# snesio.net
KiCad netlist of a schematic drawn in Altium Designer
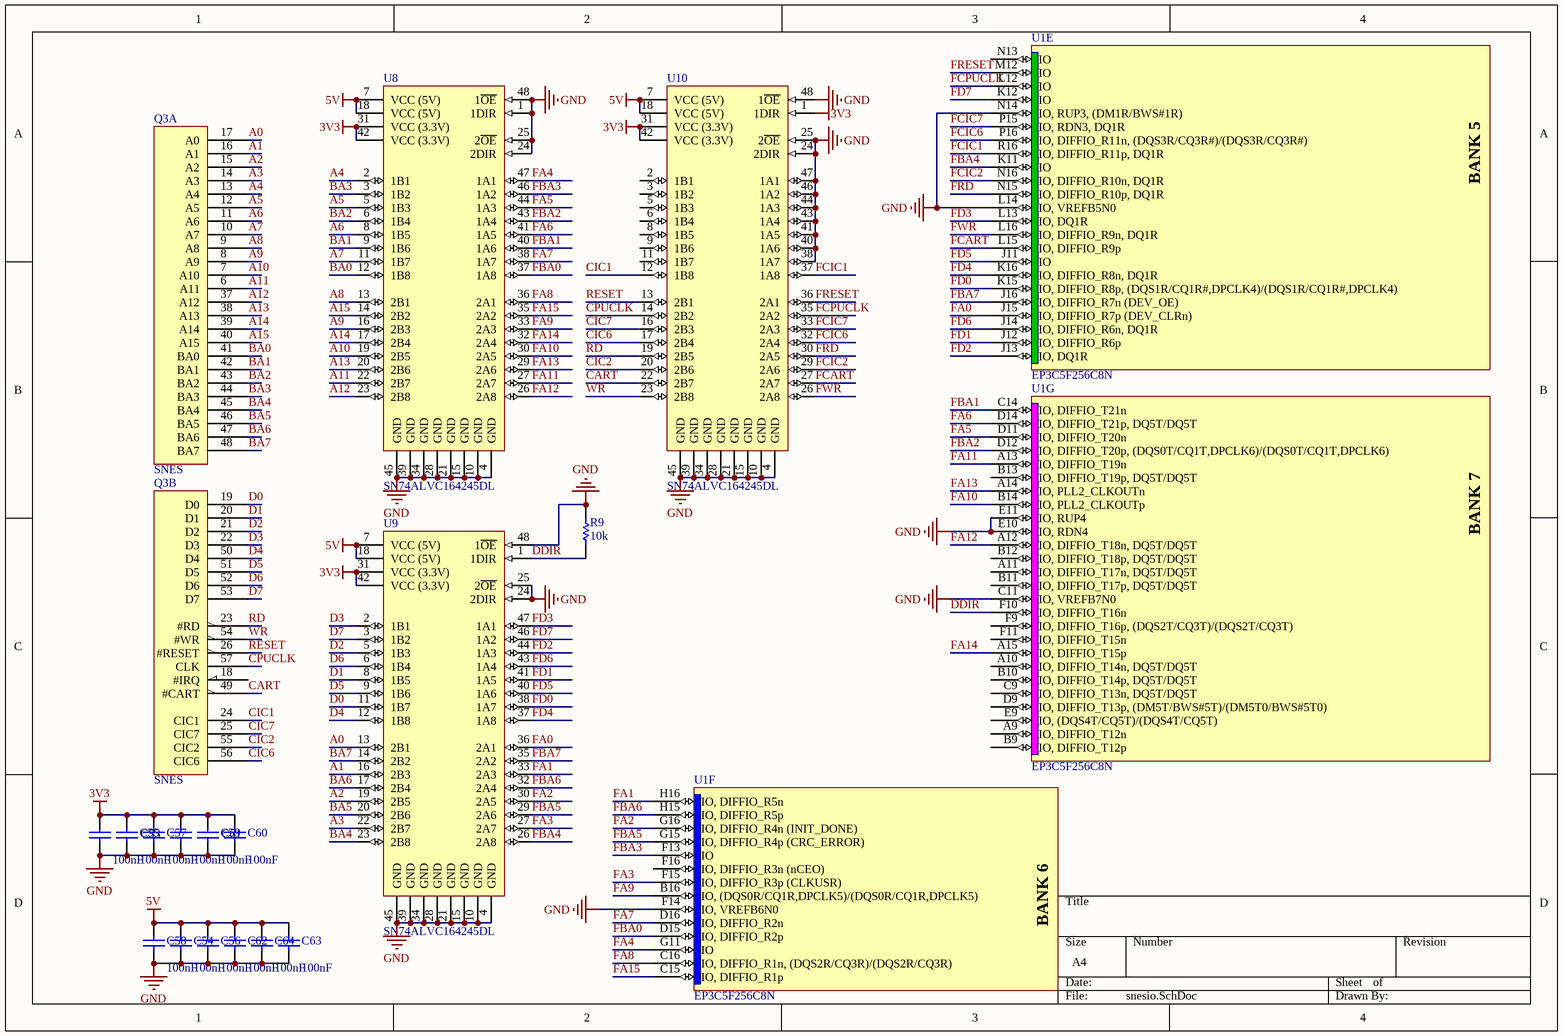
[diagram p0: snesio.SchDoc]

(export (version "E")
  (design (tool "Eeschema 10.0.6"))
  (components
    (comp (ref "C53")
      (value "100nF")
      (footprint "CAPC1005X06L")
      (description "Capacitor")
      (fields (field (name "PUBLISHER") "Altium Limited"))
      (libsource (lib "Miscellaneous Devices") (part "Cap"))
    )
    (comp (ref "C54")
      (value "100nF")
      (footprint "CAPC1005X06L")
      (description "Capacitor")
      (fields (field (name "PUBLISHER") "Altium Limited"))
      (libsource (lib "Miscellaneous Devices") (part "Cap"))
    )
    (comp (ref "C55")
      (value "100nF")
      (footprint "CAPC1005X06L")
      (description "Capacitor")
      (fields (field (name "PUBLISHER") "Altium Limited"))
      (libsource (lib "Miscellaneous Devices") (part "Cap"))
    )
    (comp (ref "C56")
      (value "100nF")
      (footprint "CAPC1005X06L")
      (description "Capacitor")
      (fields (field (name "PUBLISHER") "Altium Limited"))
      (libsource (lib "Miscellaneous Devices") (part "Cap"))
    )
    (comp (ref "C57")
      (value "100nF")
      (footprint "CAPC1005X06L")
      (description "Capacitor")
      (fields (field (name "PUBLISHER") "Altium Limited"))
      (libsource (lib "Miscellaneous Devices") (part "Cap"))
    )
    (comp (ref "C58")
      (value "100nF")
      (footprint "CAPC1005X06L")
      (description "Capacitor")
      (fields (field (name "PUBLISHER") "Altium Limited"))
      (libsource (lib "Miscellaneous Devices") (part "Cap"))
    )
    (comp (ref "C59")
      (value "100nF")
      (footprint "CAPC1005X06L")
      (description "Capacitor")
      (fields (field (name "PUBLISHER") "Altium Limited"))
      (libsource (lib "Miscellaneous Devices") (part "Cap"))
    )
    (comp (ref "C60")
      (value "100nF")
      (footprint "CAPC1005X06L")
      (description "Capacitor")
      (fields (field (name "PUBLISHER") "Altium Limited"))
      (libsource (lib "Miscellaneous Devices") (part "Cap"))
    )
    (comp (ref "C61")
      (value "100nF")
      (footprint "CAPC1005X06L")
      (description "Capacitor")
      (fields (field (name "PUBLISHER") "Altium Limited"))
      (libsource (lib "Miscellaneous Devices") (part "Cap"))
    )
    (comp (ref "C62")
      (value "100nF")
      (footprint "CAPC1005X06L")
      (description "Capacitor")
      (fields (field (name "PUBLISHER") "Altium Limited"))
      (libsource (lib "Miscellaneous Devices") (part "Cap"))
    )
    (comp (ref "C63")
      (value "100nF")
      (footprint "CAPC1005X06L")
      (description "Capacitor")
      (fields (field (name "PUBLISHER") "Altium Limited"))
      (libsource (lib "Miscellaneous Devices") (part "Cap"))
    )
    (comp (ref "C64")
      (value "100nF")
      (footprint "CAPC1005X06L")
      (description "Capacitor")
      (fields (field (name "PUBLISHER") "Altium Limited"))
      (libsource (lib "Miscellaneous Devices") (part "Cap"))
    )
    (comp (ref "Q3") (value "SNES") (footprint "SNES") (libsource (lib "parts") (part "SNES")))
    (comp (ref "R9")
      (value "10k")
      (footprint "RESC2012X70N")
      (description "Resistor")
      (fields (field (name "Comment") "Res1") (field (name "PUBLISHER") "Altium Limited"))
      (libsource (lib "Miscellaneous Devices") (part "Res1"))
    )
    (comp (ref "U1")
      (value "EP3C5F256C8N")
      (footprint "FBGA256-2")
      (fields (field (name "PUBLISHER") "Altium Limited"))
      (libsource (lib "Altera Cyclone III") (part "EP3C5F256C8N"))
    )
    (comp (ref "U8")
      (value "SN74ALVC164245DL")
      (footprint "DL048")
      (description "16-Bit 3.3-V to 5-V Level Shifting Transceiver with 3-State Outputs")
      (fields (field (name "PUBLISHER") "Altium Limited"))
      (libsource (lib "TI Interface Line Transceiver") (part "SN74ALVC164245DL"))
    )
    (comp (ref "U9")
      (value "SN74ALVC164245DL")
      (footprint "DL048")
      (description "16-Bit 3.3-V to 5-V Level Shifting Transceiver with 3-State Outputs")
      (fields (field (name "PUBLISHER") "Altium Limited"))
      (libsource (lib "TI Interface Line Transceiver") (part "SN74ALVC164245DL"))
    )
    (comp (ref "U10")
      (value "SN74ALVC164245DL")
      (footprint "DL048")
      (description "16-Bit 3.3-V to 5-V Level Shifting Transceiver with 3-State Outputs")
      (fields (field (name "PUBLISHER") "Altium Limited"))
      (libsource (lib "TI Interface Line Transceiver") (part "SN74ALVC164245DL"))
    )
  )
  (nets
    (net (code "1") (name "/A0") (class "Default")
      (node (ref "Q3") (pin "17") (pinfunction "A0_17") (pintype "passive"))
      (node (ref "U9") (pin "13") (pinfunction "2B1_13") (pintype "bidirectional"))
    )
    (net (code "2") (name "/A1") (class "Default")
      (node (ref "Q3") (pin "16") (pinfunction "A1_16") (pintype "passive"))
      (node (ref "U9") (pin "16") (pinfunction "2B3_16") (pintype "bidirectional"))
    )
    (net (code "3") (name "/A2") (class "Default")
      (node (ref "Q3") (pin "15") (pinfunction "A2_15") (pintype "passive"))
      (node (ref "U9") (pin "19") (pinfunction "2B5_19") (pintype "bidirectional"))
    )
    (net (code "4") (name "/A3") (class "Default")
      (node (ref "Q3") (pin "14") (pinfunction "A3_14") (pintype "passive"))
      (node (ref "U9") (pin "22") (pinfunction "2B7_22") (pintype "bidirectional"))
    )
    (net (code "5") (name "/A4") (class "Default")
      (node (ref "Q3") (pin "13") (pinfunction "A4_13") (pintype "passive"))
      (node (ref "U8") (pin "2") (pinfunction "1B1_2") (pintype "bidirectional"))
    )
    (net (code "6") (name "/A5") (class "Default")
      (node (ref "Q3") (pin "12") (pinfunction "A5_12") (pintype "passive"))
      (node (ref "U8") (pin "5") (pinfunction "1B3_5") (pintype "bidirectional"))
    )
    (net (code "7") (name "/A6") (class "Default")
      (node (ref "Q3") (pin "11") (pinfunction "A6_11") (pintype "passive"))
      (node (ref "U8") (pin "8") (pinfunction "1B5_8") (pintype "bidirectional"))
    )
    (net (code "8") (name "/A7") (class "Default")
      (node (ref "Q3") (pin "10") (pinfunction "A7_10") (pintype "passive"))
      (node (ref "U8") (pin "11") (pinfunction "1B7_11") (pintype "bidirectional"))
    )
    (net (code "9") (name "/A8") (class "Default")
      (node (ref "Q3") (pin "9") (pinfunction "A8_9") (pintype "passive"))
      (node (ref "U8") (pin "13") (pinfunction "2B1_13") (pintype "bidirectional"))
    )
    (net (code "10") (name "/A9") (class "Default")
      (node (ref "Q3") (pin "8") (pinfunction "A9_8") (pintype "passive"))
      (node (ref "U8") (pin "16") (pinfunction "2B3_16") (pintype "bidirectional"))
    )
    (net (code "11") (name "/A10") (class "Default")
      (node (ref "Q3") (pin "7") (pinfunction "A10_7") (pintype "passive"))
      (node (ref "U8") (pin "19") (pinfunction "2B5_19") (pintype "bidirectional"))
    )
    (net (code "12") (name "/A11") (class "Default")
      (node (ref "Q3") (pin "6") (pinfunction "A11_6") (pintype "passive"))
      (node (ref "U8") (pin "22") (pinfunction "2B7_22") (pintype "bidirectional"))
    )
    (net (code "13") (name "/A12") (class "Default")
      (node (ref "Q3") (pin "37") (pinfunction "A12_37") (pintype "passive"))
      (node (ref "U8") (pin "23") (pinfunction "2B8_23") (pintype "bidirectional"))
    )
    (net (code "14") (name "/A13") (class "Default")
      (node (ref "Q3") (pin "38") (pinfunction "A13_38") (pintype "passive"))
      (node (ref "U8") (pin "20") (pinfunction "2B6_20") (pintype "bidirectional"))
    )
    (net (code "15") (name "/A14") (class "Default")
      (node (ref "Q3") (pin "39") (pinfunction "A14_39") (pintype "passive"))
      (node (ref "U8") (pin "17") (pinfunction "2B4_17") (pintype "bidirectional"))
    )
    (net (code "16") (name "/A15") (class "Default")
      (node (ref "Q3") (pin "40") (pinfunction "A15_40") (pintype "passive"))
      (node (ref "U8") (pin "14") (pinfunction "2B2_14") (pintype "bidirectional"))
    )
    (net (code "17") (name "/BA0") (class "Default")
      (node (ref "Q3") (pin "41") (pinfunction "BA0_41") (pintype "passive"))
      (node (ref "U8") (pin "12") (pinfunction "1B8_12") (pintype "bidirectional"))
    )
    (net (code "18") (name "/BA1") (class "Default")
      (node (ref "Q3") (pin "42") (pinfunction "BA1_42") (pintype "passive"))
      (node (ref "U8") (pin "9") (pinfunction "1B6_9") (pintype "bidirectional"))
    )
    (net (code "19") (name "/BA2") (class "Default")
      (node (ref "Q3") (pin "43") (pinfunction "BA2_43") (pintype "passive"))
      (node (ref "U8") (pin "6") (pinfunction "1B4_6") (pintype "bidirectional"))
    )
    (net (code "20") (name "/BA3") (class "Default")
      (node (ref "Q3") (pin "44") (pinfunction "BA3_44") (pintype "passive"))
      (node (ref "U8") (pin "3") (pinfunction "1B2_3") (pintype "bidirectional"))
    )
    (net (code "21") (name "/BA4") (class "Default")
      (node (ref "Q3") (pin "45") (pinfunction "BA4_45") (pintype "passive"))
      (node (ref "U9") (pin "23") (pinfunction "2B8_23") (pintype "bidirectional"))
    )
    (net (code "22") (name "/BA5") (class "Default")
      (node (ref "Q3") (pin "46") (pinfunction "BA5_46") (pintype "passive"))
      (node (ref "U9") (pin "20") (pinfunction "2B6_20") (pintype "bidirectional"))
    )
    (net (code "23") (name "/BA6") (class "Default")
      (node (ref "Q3") (pin "47") (pinfunction "BA6_47") (pintype "passive"))
      (node (ref "U9") (pin "17") (pinfunction "2B4_17") (pintype "bidirectional"))
    )
    (net (code "24") (name "/BA7") (class "Default")
      (node (ref "Q3") (pin "48") (pinfunction "BA7_48") (pintype "passive"))
      (node (ref "U9") (pin "14") (pinfunction "2B2_14") (pintype "bidirectional"))
    )
    (net (code "25") (name "/CART") (class "Default")
      (node (ref "Q3") (pin "49") (pinfunction "#CART_49") (pintype "passive"))
      (node (ref "U10") (pin "22") (pinfunction "2B7_22") (pintype "bidirectional"))
    )
    (net (code "26") (name "/CIC1") (class "Default")
      (node (ref "Q3") (pin "24") (pinfunction "CIC1_24") (pintype "passive"))
      (node (ref "U10") (pin "12") (pinfunction "1B8_12") (pintype "bidirectional"))
    )
    (net (code "27") (name "/CIC2") (class "Default")
      (node (ref "Q3") (pin "55") (pinfunction "CIC2_55") (pintype "passive"))
      (node (ref "U10") (pin "20") (pinfunction "2B6_20") (pintype "bidirectional"))
    )
    (net (code "28") (name "/CIC6") (class "Default")
      (node (ref "Q3") (pin "56") (pinfunction "CIC6_56") (pintype "passive"))
      (node (ref "U10") (pin "17") (pinfunction "2B4_17") (pintype "bidirectional"))
    )
    (net (code "29") (name "/CIC7") (class "Default")
      (node (ref "Q3") (pin "25") (pinfunction "CIC7_25") (pintype "passive"))
      (node (ref "U10") (pin "16") (pinfunction "2B3_16") (pintype "bidirectional"))
    )
    (net (code "30") (name "/CPUCLK") (class "Default")
      (node (ref "Q3") (pin "57") (pinfunction "CLK_57") (pintype "passive"))
      (node (ref "U10") (pin "14") (pinfunction "2B2_14") (pintype "bidirectional"))
    )
    (net (code "31") (name "/D0") (class "Default")
      (node (ref "Q3") (pin "19") (pinfunction "D0_19") (pintype "passive"))
      (node (ref "U9") (pin "11") (pinfunction "1B7_11") (pintype "bidirectional"))
    )
    (net (code "32") (name "/D1") (class "Default")
      (node (ref "Q3") (pin "20") (pinfunction "D1_20") (pintype "passive"))
      (node (ref "U9") (pin "8") (pinfunction "1B5_8") (pintype "bidirectional"))
    )
    (net (code "33") (name "/D2") (class "Default")
      (node (ref "Q3") (pin "21") (pinfunction "D2_21") (pintype "passive"))
      (node (ref "U9") (pin "5") (pinfunction "1B3_5") (pintype "bidirectional"))
    )
    (net (code "34") (name "/D3") (class "Default")
      (node (ref "Q3") (pin "22") (pinfunction "D3_22") (pintype "passive"))
      (node (ref "U9") (pin "2") (pinfunction "1B1_2") (pintype "bidirectional"))
    )
    (net (code "35") (name "/D4") (class "Default")
      (node (ref "Q3") (pin "50") (pinfunction "D4_50") (pintype "passive"))
      (node (ref "U9") (pin "12") (pinfunction "1B8_12") (pintype "bidirectional"))
    )
    (net (code "36") (name "/D5") (class "Default")
      (node (ref "Q3") (pin "51") (pinfunction "D5_51") (pintype "passive"))
      (node (ref "U9") (pin "9") (pinfunction "1B6_9") (pintype "bidirectional"))
    )
    (net (code "37") (name "/D6") (class "Default")
      (node (ref "Q3") (pin "52") (pinfunction "D6_52") (pintype "passive"))
      (node (ref "U9") (pin "6") (pinfunction "1B4_6") (pintype "bidirectional"))
    )
    (net (code "38") (name "/D7") (class "Default")
      (node (ref "Q3") (pin "53") (pinfunction "D7_53") (pintype "passive"))
      (node (ref "U9") (pin "3") (pinfunction "1B2_3") (pintype "bidirectional"))
    )
    (net (code "39") (name "/DDIR") (class "Default")
      (node (ref "R9") (pin "2") (pinfunction "2_2") (pintype "passive"))
      (node (ref "U1") (pin "F10") (pinfunction "IO,_DIFFIO_T16n_F10") (pintype "bidirectional"))
      (node (ref "U9") (pin "1") (pinfunction "1DIR_1") (pintype "input"))
    )
    (net (code "40") (name "/FA0") (class "Default")
      (node (ref "U1") (pin "J15") (pinfunction "IO,_DIFFIO_R7p_(DEV_CLRn)_J15") (pintype "bidirectional"))
      (node (ref "U9") (pin "36") (pinfunction "2A1_36") (pintype "bidirectional"))
    )
    (net (code "41") (name "/FA1") (class "Default")
      (node (ref "U1") (pin "H16") (pinfunction "IO,_DIFFIO_R5n_H16") (pintype "bidirectional"))
      (node (ref "U9") (pin "33") (pinfunction "2A3_33") (pintype "bidirectional"))
    )
    (net (code "42") (name "/FA2") (class "Default")
      (node (ref "U1") (pin "G16") (pinfunction "IO,_DIFFIO_R4n_(INIT_DONE)_G16") (pintype "bidirectional"))
      (node (ref "U9") (pin "30") (pinfunction "2A5_30") (pintype "bidirectional"))
    )
    (net (code "43") (name "/FA3") (class "Default")
      (node (ref "U1") (pin "F15") (pinfunction "IO,_DIFFIO_R3p_(CLKUSR)_F15") (pintype "bidirectional"))
      (node (ref "U9") (pin "27") (pinfunction "2A7_27") (pintype "bidirectional"))
    )
    (net (code "44") (name "/FA4") (class "Default")
      (node (ref "U1") (pin "G11") (pinfunction "IO_G11") (pintype "bidirectional"))
      (node (ref "U8") (pin "47") (pinfunction "1A1_47") (pintype "bidirectional"))
    )
    (net (code "45") (name "/FA5") (class "Default")
      (node (ref "U1") (pin "D11") (pinfunction "IO,_DIFFIO_T20n_D11") (pintype "bidirectional"))
      (node (ref "U8") (pin "44") (pinfunction "1A3_44") (pintype "bidirectional"))
    )
    (net (code "46") (name "/FA6") (class "Default")
      (node (ref "U1") (pin "D14") (pinfunction "IO,_DIFFIO_T21p,_DQ5T/DQ5T_D14") (pintype "bidirectional"))
      (node (ref "U8") (pin "41") (pinfunction "1A5_41") (pintype "bidirectional"))
    )
    (net (code "47") (name "/FA7") (class "Default")
      (node (ref "U1") (pin "D16") (pinfunction "IO,_DIFFIO_R2n_D16") (pintype "bidirectional"))
      (node (ref "U8") (pin "38") (pinfunction "1A7_38") (pintype "bidirectional"))
    )
    (net (code "48") (name "/FA8") (class "Default")
      (node (ref "U1") (pin "C16") (pinfunction "IO,_DIFFIO_R1n,_(DQS2R/CQ3R)/(DQS2R/CQ3R)_C16") (pintype "bidirectional"))
      (node (ref "U8") (pin "36") (pinfunction "2A1_36") (pintype "bidirectional"))
    )
    (net (code "49") (name "/FA9") (class "Default")
      (node (ref "U1") (pin "B16") (pinfunction "IO,_(DQS0R/CQ1R,DPCLK5)/(DQS0R/CQ1R,DPCLK5)_B16") (pintype "bidirectional"))
      (node (ref "U8") (pin "33") (pinfunction "2A3_33") (pintype "bidirectional"))
    )
    (net (code "50") (name "/FA10") (class "Default")
      (node (ref "U1") (pin "B14") (pinfunction "IO,_PLL2_CLKOUTp_B14") (pintype "bidirectional"))
      (node (ref "U8") (pin "30") (pinfunction "2A5_30") (pintype "bidirectional"))
    )
    (net (code "51") (name "/FA11") (class "Default")
      (node (ref "U1") (pin "A13") (pinfunction "IO,_DIFFIO_T19n_A13") (pintype "bidirectional"))
      (node (ref "U8") (pin "27") (pinfunction "2A7_27") (pintype "bidirectional"))
    )
    (net (code "52") (name "/FA12") (class "Default")
      (node (ref "U1") (pin "A12") (pinfunction "IO,_DIFFIO_T18n,_DQ5T/DQ5T_A12") (pintype "bidirectional"))
      (node (ref "U8") (pin "26") (pinfunction "2A8_26") (pintype "bidirectional"))
    )
    (net (code "53") (name "/FA13") (class "Default")
      (node (ref "U1") (pin "A14") (pinfunction "IO,_PLL2_CLKOUTn_A14") (pintype "bidirectional"))
      (node (ref "U8") (pin "29") (pinfunction "2A6_29") (pintype "bidirectional"))
    )
    (net (code "54") (name "/FA14") (class "Default")
      (node (ref "U1") (pin "A15") (pinfunction "IO,_DIFFIO_T15p_A15") (pintype "bidirectional"))
      (node (ref "U8") (pin "32") (pinfunction "2A4_32") (pintype "bidirectional"))
    )
    (net (code "55") (name "/FA15") (class "Default")
      (node (ref "U1") (pin "C15") (pinfunction "IO,_DIFFIO_R1p_C15") (pintype "bidirectional"))
      (node (ref "U8") (pin "35") (pinfunction "2A2_35") (pintype "bidirectional"))
    )
    (net (code "56") (name "/FBA0") (class "Default")
      (node (ref "U1") (pin "D15") (pinfunction "IO,_DIFFIO_R2p_D15") (pintype "bidirectional"))
      (node (ref "U8") (pin "37") (pinfunction "1A8_37") (pintype "bidirectional"))
    )
    (net (code "57") (name "/FBA1") (class "Default")
      (node (ref "U1") (pin "C14") (pinfunction "IO,_DIFFIO_T21n_C14") (pintype "bidirectional"))
      (node (ref "U8") (pin "40") (pinfunction "1A6_40") (pintype "bidirectional"))
    )
    (net (code "58") (name "/FBA2") (class "Default")
      (node (ref "U1") (pin "D12") (pinfunction "IO,_DIFFIO_T20p,_(DQS0T/CQ1T,DPCLK6)/(DQS0T/CQ1T,DPCLK6)_D12") (pintype "bidirectional"))
      (node (ref "U8") (pin "43") (pinfunction "1A4_43") (pintype "bidirectional"))
    )
    (net (code "59") (name "/FBA3") (class "Default")
      (node (ref "U1") (pin "F13") (pinfunction "IO_F13") (pintype "bidirectional"))
      (node (ref "U8") (pin "46") (pinfunction "1A2_46") (pintype "bidirectional"))
    )
    (net (code "60") (name "/FBA4") (class "Default")
      (node (ref "U1") (pin "K11") (pinfunction "IO_K11") (pintype "bidirectional"))
      (node (ref "U9") (pin "26") (pinfunction "2A8_26") (pintype "bidirectional"))
    )
    (net (code "61") (name "/FBA5") (class "Default")
      (node (ref "U1") (pin "G15") (pinfunction "IO,_DIFFIO_R4p_(CRC_ERROR)_G15") (pintype "bidirectional"))
      (node (ref "U9") (pin "29") (pinfunction "2A6_29") (pintype "bidirectional"))
    )
    (net (code "62") (name "/FBA6") (class "Default")
      (node (ref "U1") (pin "H15") (pinfunction "IO,_DIFFIO_R5p_H15") (pintype "bidirectional"))
      (node (ref "U9") (pin "32") (pinfunction "2A4_32") (pintype "bidirectional"))
    )
    (net (code "63") (name "/FBA7") (class "Default")
      (node (ref "U1") (pin "J16") (pinfunction "IO,_DIFFIO_R7n_(DEV_OE)_J16") (pintype "bidirectional"))
      (node (ref "U9") (pin "35") (pinfunction "2A2_35") (pintype "bidirectional"))
    )
    (net (code "64") (name "/FCART") (class "Default")
      (node (ref "U1") (pin "L15") (pinfunction "IO,_DIFFIO_R9p_L15") (pintype "bidirectional"))
      (node (ref "U10") (pin "27") (pinfunction "2A7_27") (pintype "bidirectional"))
    )
    (net (code "65") (name "/FCIC1") (class "Default")
      (node (ref "U1") (pin "R16") (pinfunction "IO,_DIFFIO_R11p,_DQ1R_R16") (pintype "bidirectional"))
      (node (ref "U10") (pin "37") (pinfunction "1A8_37") (pintype "bidirectional"))
    )
    (net (code "66") (name "/FCIC2") (class "Default")
      (node (ref "U1") (pin "N16") (pinfunction "IO,_DIFFIO_R10n,_DQ1R_N16") (pintype "bidirectional"))
      (node (ref "U10") (pin "29") (pinfunction "2A6_29") (pintype "bidirectional"))
    )
    (net (code "67") (name "/FCIC6") (class "Default")
      (node (ref "U1") (pin "P16") (pinfunction "IO,_DIFFIO_R11n,_(DQS3R/CQ3R#)/(DQS3R/CQ3R#)_P16") (pintype "bidirectional"))
      (node (ref "U10") (pin "32") (pinfunction "2A4_32") (pintype "bidirectional"))
    )
    (net (code "68") (name "/FCIC7") (class "Default")
      (node (ref "U1") (pin "P15") (pinfunction "IO,_RDN3,_DQ1R_P15") (pintype "bidirectional"))
      (node (ref "U10") (pin "33") (pinfunction "2A3_33") (pintype "bidirectional"))
    )
    (net (code "69") (name "/FCPUCLK") (class "Default")
      (node (ref "U1") (pin "L12") (pinfunction "IO_L12") (pintype "bidirectional"))
      (node (ref "U10") (pin "35") (pinfunction "2A2_35") (pintype "bidirectional"))
    )
    (net (code "70") (name "/FD0") (class "Default")
      (node (ref "U1") (pin "K15") (pinfunction "IO,_DIFFIO_R8p,_(DQS1R/CQ1R#,DPCLK4)/(DQS1R/CQ1R#,DPCLK4)_K15") (pintype "bidirectional"))
      (node (ref "U9") (pin "38") (pinfunction "1A7_38") (pintype "bidirectional"))
    )
    (net (code "71") (name "/FD1") (class "Default")
      (node (ref "U1") (pin "J12") (pinfunction "IO,_DIFFIO_R6p_J12") (pintype "bidirectional"))
      (node (ref "U9") (pin "41") (pinfunction "1A5_41") (pintype "bidirectional"))
    )
    (net (code "72") (name "/FD2") (class "Default")
      (node (ref "U1") (pin "J13") (pinfunction "IO,_DQ1R_J13") (pintype "bidirectional"))
      (node (ref "U9") (pin "44") (pinfunction "1A3_44") (pintype "bidirectional"))
    )
    (net (code "73") (name "/FD3") (class "Default")
      (node (ref "U1") (pin "L13") (pinfunction "IO,_DQ1R_L13") (pintype "bidirectional"))
      (node (ref "U9") (pin "47") (pinfunction "1A1_47") (pintype "bidirectional"))
    )
    (net (code "74") (name "/FD4") (class "Default")
      (node (ref "U1") (pin "K16") (pinfunction "IO,_DIFFIO_R8n,_DQ1R_K16") (pintype "bidirectional"))
      (node (ref "U9") (pin "37") (pinfunction "1A8_37") (pintype "bidirectional"))
    )
    (net (code "75") (name "/FD5") (class "Default")
      (node (ref "U1") (pin "J11") (pinfunction "IO_J11") (pintype "bidirectional"))
      (node (ref "U9") (pin "40") (pinfunction "1A6_40") (pintype "bidirectional"))
    )
    (net (code "76") (name "/FD6") (class "Default")
      (node (ref "U1") (pin "J14") (pinfunction "IO,_DIFFIO_R6n,_DQ1R_J14") (pintype "bidirectional"))
      (node (ref "U9") (pin "43") (pinfunction "1A4_43") (pintype "bidirectional"))
    )
    (net (code "77") (name "/FD7") (class "Default")
      (node (ref "U1") (pin "K12") (pinfunction "IO_K12") (pintype "bidirectional"))
      (node (ref "U9") (pin "46") (pinfunction "1A2_46") (pintype "bidirectional"))
    )
    (net (code "78") (name "/FRD") (class "Default")
      (node (ref "U1") (pin "N15") (pinfunction "IO,_DIFFIO_R10p,_DQ1R_N15") (pintype "bidirectional"))
      (node (ref "U10") (pin "30") (pinfunction "2A5_30") (pintype "bidirectional"))
    )
    (net (code "79") (name "/FRESET") (class "Default")
      (node (ref "U1") (pin "M12") (pinfunction "IO_M12") (pintype "bidirectional"))
      (node (ref "U10") (pin "36") (pinfunction "2A1_36") (pintype "bidirectional"))
    )
    (net (code "80") (name "/FWR") (class "Default")
      (node (ref "U1") (pin "L16") (pinfunction "IO,_DIFFIO_R9n,_DQ1R_L16") (pintype "bidirectional"))
      (node (ref "U10") (pin "26") (pinfunction "2A8_26") (pintype "bidirectional"))
    )
    (net (code "81") (name "/RD") (class "Default")
      (node (ref "Q3") (pin "23") (pinfunction "#RD_23") (pintype "passive"))
      (node (ref "U10") (pin "19") (pinfunction "2B5_19") (pintype "bidirectional"))
    )
    (net (code "82") (name "/RESET") (class "Default")
      (node (ref "Q3") (pin "26") (pinfunction "#RESET_26") (pintype "passive"))
      (node (ref "U10") (pin "13") (pinfunction "2B1_13") (pintype "bidirectional"))
    )
    (net (code "83") (name "/WR") (class "Default")
      (node (ref "Q3") (pin "54") (pinfunction "#WR_54") (pintype "passive"))
      (node (ref "U10") (pin "23") (pinfunction "2B8_23") (pintype "bidirectional"))
    )
    (net (code "84") (name "3V3") (class "Default")
      (node (ref "C53") (pin "2") (pinfunction "2_2") (pintype "passive"))
      (node (ref "C55") (pin "2") (pinfunction "2_2") (pintype "passive"))
      (node (ref "C57") (pin "2") (pinfunction "2_2") (pintype "passive"))
      (node (ref "C59") (pin "2") (pinfunction "2_2") (pintype "passive"))
      (node (ref "C60") (pin "2") (pinfunction "2_2") (pintype "passive"))
      (node (ref "C61") (pin "2") (pinfunction "2_2") (pintype "passive"))
      (node (ref "U10") (pin "1") (pinfunction "1DIR_1") (pintype "input"))
      (node (ref "U10") (pin "31") (pinfunction "VCC_(3.3V)_31") (pintype "power_in"))
      (node (ref "U10") (pin "42") (pinfunction "VCC_(3.3V)_42") (pintype "power_in"))
      (node (ref "U8") (pin "31") (pinfunction "VCC_(3.3V)_31") (pintype "power_in"))
      (node (ref "U8") (pin "42") (pinfunction "VCC_(3.3V)_42") (pintype "power_in"))
      (node (ref "U9") (pin "31") (pinfunction "VCC_(3.3V)_31") (pintype "power_in"))
      (node (ref "U9") (pin "42") (pinfunction "VCC_(3.3V)_42") (pintype "power_in"))
    )
    (net (code "85") (name "5V") (class "Default")
      (node (ref "C54") (pin "2") (pinfunction "2_2") (pintype "passive"))
      (node (ref "C56") (pin "2") (pinfunction "2_2") (pintype "passive"))
      (node (ref "C58") (pin "2") (pinfunction "2_2") (pintype "passive"))
      (node (ref "C62") (pin "2") (pinfunction "2_2") (pintype "passive"))
      (node (ref "C63") (pin "2") (pinfunction "2_2") (pintype "passive"))
      (node (ref "C64") (pin "2") (pinfunction "2_2") (pintype "passive"))
      (node (ref "U10") (pin "18") (pinfunction "VCC_(5V)_18") (pintype "power_in"))
      (node (ref "U10") (pin "7") (pinfunction "VCC_(5V)_7") (pintype "power_in"))
      (node (ref "U8") (pin "18") (pinfunction "VCC_(5V)_18") (pintype "power_in"))
      (node (ref "U8") (pin "7") (pinfunction "VCC_(5V)_7") (pintype "power_in"))
      (node (ref "U9") (pin "18") (pinfunction "VCC_(5V)_18") (pintype "power_in"))
      (node (ref "U9") (pin "7") (pinfunction "VCC_(5V)_7") (pintype "power_in"))
    )
    (net (code "86") (name "GND") (class "Default")
      (node (ref "C53") (pin "1") (pinfunction "1_1") (pintype "passive"))
      (node (ref "C54") (pin "1") (pinfunction "1_1") (pintype "passive"))
      (node (ref "C55") (pin "1") (pinfunction "1_1") (pintype "passive"))
      (node (ref "C56") (pin "1") (pinfunction "1_1") (pintype "passive"))
      (node (ref "C57") (pin "1") (pinfunction "1_1") (pintype "passive"))
      (node (ref "C58") (pin "1") (pinfunction "1_1") (pintype "passive"))
      (node (ref "C59") (pin "1") (pinfunction "1_1") (pintype "passive"))
      (node (ref "C60") (pin "1") (pinfunction "1_1") (pintype "passive"))
      (node (ref "C61") (pin "1") (pinfunction "1_1") (pintype "passive"))
      (node (ref "C62") (pin "1") (pinfunction "1_1") (pintype "passive"))
      (node (ref "C63") (pin "1") (pinfunction "1_1") (pintype "passive"))
      (node (ref "C64") (pin "1") (pinfunction "1_1") (pintype "passive"))
      (node (ref "R9") (pin "1") (pinfunction "1_1") (pintype "passive"))
      (node (ref "U1") (pin "C11") (pinfunction "IO,_VREFB7N0_C11") (pintype "bidirectional"))
      (node (ref "U1") (pin "E10") (pinfunction "IO,_RDN4_E10") (pintype "bidirectional"))
      (node (ref "U1") (pin "E11") (pinfunction "IO,_RUP4_E11") (pintype "bidirectional"))
      (node (ref "U1") (pin "F14") (pinfunction "IO,_VREFB6N0_F14") (pintype "bidirectional"))
      (node (ref "U1") (pin "L14") (pinfunction "IO,_VREFB5N0_L14") (pintype "bidirectional"))
      (node (ref "U1") (pin "N14") (pinfunction "IO,_RUP3,_(DM1R/BWS#1R)_N14") (pintype "bidirectional"))
      (node (ref "U10") (pin "10") (pinfunction "GND_10") (pintype "power_in"))
      (node (ref "U10") (pin "15") (pinfunction "GND_15") (pintype "power_in"))
      (node (ref "U10") (pin "21") (pinfunction "GND_21") (pintype "power_in"))
      (node (ref "U10") (pin "24") (pinfunction "2DIR_24") (pintype "input"))
      (node (ref "U10") (pin "25") (pinfunction "2~{OE}_25") (pintype "input"))
      (node (ref "U10") (pin "28") (pinfunction "GND_28") (pintype "power_in"))
      (node (ref "U10") (pin "34") (pinfunction "GND_34") (pintype "power_in"))
      (node (ref "U10") (pin "38") (pinfunction "1A7_38") (pintype "bidirectional"))
      (node (ref "U10") (pin "39") (pinfunction "GND_39") (pintype "power_in"))
      (node (ref "U10") (pin "4") (pinfunction "GND_4") (pintype "power_in"))
      (node (ref "U10") (pin "40") (pinfunction "1A6_40") (pintype "bidirectional"))
      (node (ref "U10") (pin "41") (pinfunction "1A5_41") (pintype "bidirectional"))
      (node (ref "U10") (pin "43") (pinfunction "1A4_43") (pintype "bidirectional"))
      (node (ref "U10") (pin "44") (pinfunction "1A3_44") (pintype "bidirectional"))
      (node (ref "U10") (pin "45") (pinfunction "GND_45") (pintype "power_in"))
      (node (ref "U10") (pin "46") (pinfunction "1A2_46") (pintype "bidirectional"))
      (node (ref "U10") (pin "47") (pinfunction "1A1_47") (pintype "bidirectional"))
      (node (ref "U10") (pin "48") (pinfunction "1~{OE}_48") (pintype "input"))
      (node (ref "U8") (pin "1") (pinfunction "1DIR_1") (pintype "input"))
      (node (ref "U8") (pin "10") (pinfunction "GND_10") (pintype "power_in"))
      (node (ref "U8") (pin "15") (pinfunction "GND_15") (pintype "power_in"))
      (node (ref "U8") (pin "21") (pinfunction "GND_21") (pintype "power_in"))
      (node (ref "U8") (pin "24") (pinfunction "2DIR_24") (pintype "input"))
      (node (ref "U8") (pin "25") (pinfunction "2~{OE}_25") (pintype "input"))
      (node (ref "U8") (pin "28") (pinfunction "GND_28") (pintype "power_in"))
      (node (ref "U8") (pin "34") (pinfunction "GND_34") (pintype "power_in"))
      (node (ref "U8") (pin "39") (pinfunction "GND_39") (pintype "power_in"))
      (node (ref "U8") (pin "4") (pinfunction "GND_4") (pintype "power_in"))
      (node (ref "U8") (pin "45") (pinfunction "GND_45") (pintype "power_in"))
      (node (ref "U8") (pin "48") (pinfunction "1~{OE}_48") (pintype "input"))
      (node (ref "U9") (pin "10") (pinfunction "GND_10") (pintype "power_in"))
      (node (ref "U9") (pin "15") (pinfunction "GND_15") (pintype "power_in"))
      (node (ref "U9") (pin "21") (pinfunction "GND_21") (pintype "power_in"))
      (node (ref "U9") (pin "24") (pinfunction "2DIR_24") (pintype "input"))
      (node (ref "U9") (pin "25") (pinfunction "2~{OE}_25") (pintype "input"))
      (node (ref "U9") (pin "28") (pinfunction "GND_28") (pintype "power_in"))
      (node (ref "U9") (pin "34") (pinfunction "GND_34") (pintype "power_in"))
      (node (ref "U9") (pin "39") (pinfunction "GND_39") (pintype "power_in"))
      (node (ref "U9") (pin "4") (pinfunction "GND_4") (pintype "power_in"))
      (node (ref "U9") (pin "45") (pinfunction "GND_45") (pintype "power_in"))
      (node (ref "U9") (pin "48") (pinfunction "1~{OE}_48") (pintype "input"))
    )
    (net (code "87") (name "unconnected-(Q3B-#IRQ-Pad18)") (class "Default")
      (node (ref "Q3") (pin "18") (pinfunction "#IRQ_18") (pintype "passive"))
    )
    (net (code "88") (name "unconnected-(U1E-IO-PadN13)") (class "Default")
      (node (ref "U1") (pin "N13") (pinfunction "IO_N13") (pintype "bidirectional"))
    )
    (net (code "89") (name "unconnected-(U1F-IO,_DIFFIO_R3n_(nCEO)-PadF16)") (class "Default")
      (node (ref "U1") (pin "F16") (pinfunction "IO,_DIFFIO_R3n_(nCEO)_F16") (pintype "bidirectional"))
    )
    (net (code "90") (name "unconnected-(U1G-IO,_(DQS4T{slash}CQ5T){slash}(DQS4T{slash}CQ5T)-PadE9)") (class "Default")
      (node (ref "U1") (pin "E9") (pinfunction "IO,_(DQS4T/CQ5T)/(DQS4T/CQ5T)_E9") (pintype "bidirectional"))
    )
    (net (code "91") (name "unconnected-(U1G-IO,_DIFFIO_T12n-PadA9)") (class "Default")
      (node (ref "U1") (pin "A9") (pinfunction "IO,_DIFFIO_T12n_A9") (pintype "bidirectional"))
    )
    (net (code "92") (name "unconnected-(U1G-IO,_DIFFIO_T12p-PadB9)") (class "Default")
      (node (ref "U1") (pin "B9") (pinfunction "IO,_DIFFIO_T12p_B9") (pintype "bidirectional"))
    )
    (net (code "93") (name "unconnected-(U1G-IO,_DIFFIO_T13n,_DQ5T{slash}DQ5T-PadC9)") (class "Default")
      (node (ref "U1") (pin "C9") (pinfunction "IO,_DIFFIO_T13n,_DQ5T/DQ5T_C9") (pintype "bidirectional"))
    )
    (net (code "94") (name "unconnected-(U1G-IO,_DIFFIO_T13p,_(DM5T{slash}BWS#5T){slash}(DM5T0{slash}BWS#5T0)-PadD9)") (class "Default")
      (node (ref "U1") (pin "D9") (pinfunction "IO,_DIFFIO_T13p,_(DM5T/BWS#5T)/(DM5T0/BWS#5T0)_D9") (pintype "bidirectional"))
    )
    (net (code "95") (name "unconnected-(U1G-IO,_DIFFIO_T14n,_DQ5T{slash}DQ5T-PadA10)") (class "Default")
      (node (ref "U1") (pin "A10") (pinfunction "IO,_DIFFIO_T14n,_DQ5T/DQ5T_A10") (pintype "bidirectional"))
    )
    (net (code "96") (name "unconnected-(U1G-IO,_DIFFIO_T14p,_DQ5T{slash}DQ5T-PadB10)") (class "Default")
      (node (ref "U1") (pin "B10") (pinfunction "IO,_DIFFIO_T14p,_DQ5T/DQ5T_B10") (pintype "bidirectional"))
    )
    (net (code "97") (name "unconnected-(U1G-IO,_DIFFIO_T15n-PadF11)") (class "Default")
      (node (ref "U1") (pin "F11") (pinfunction "IO,_DIFFIO_T15n_F11") (pintype "bidirectional"))
    )
    (net (code "98") (name "unconnected-(U1G-IO,_DIFFIO_T16p,_(DQS2T{slash}CQ3T){slash}(DQS2T{slash}CQ3T)-PadF9)") (class "Default")
      (node (ref "U1") (pin "F9") (pinfunction "IO,_DIFFIO_T16p,_(DQS2T/CQ3T)/(DQS2T/CQ3T)_F9") (pintype "bidirectional"))
    )
    (net (code "99") (name "unconnected-(U1G-IO,_DIFFIO_T17n,_DQ5T{slash}DQ5T-PadA11)") (class "Default")
      (node (ref "U1") (pin "A11") (pinfunction "IO,_DIFFIO_T17n,_DQ5T/DQ5T_A11") (pintype "bidirectional"))
    )
    (net (code "100") (name "unconnected-(U1G-IO,_DIFFIO_T17p,_DQ5T{slash}DQ5T-PadB11)") (class "Default")
      (node (ref "U1") (pin "B11") (pinfunction "IO,_DIFFIO_T17p,_DQ5T/DQ5T_B11") (pintype "bidirectional"))
    )
    (net (code "101") (name "unconnected-(U1G-IO,_DIFFIO_T18p,_DQ5T{slash}DQ5T-PadB12)") (class "Default")
      (node (ref "U1") (pin "B12") (pinfunction "IO,_DIFFIO_T18p,_DQ5T/DQ5T_B12") (pintype "bidirectional"))
    )
    (net (code "102") (name "unconnected-(U1G-IO,_DIFFIO_T19p,_DQ5T{slash}DQ5T-PadB13)") (class "Default")
      (node (ref "U1") (pin "B13") (pinfunction "IO,_DIFFIO_T19p,_DQ5T/DQ5T_B13") (pintype "bidirectional"))
    )
    (net (code "103") (name "unconnected-(U10-1B1-Pad2)") (class "Default")
      (node (ref "U10") (pin "2") (pinfunction "1B1_2") (pintype "bidirectional"))
    )
    (net (code "104") (name "unconnected-(U10-1B2-Pad3)") (class "Default")
      (node (ref "U10") (pin "3") (pinfunction "1B2_3") (pintype "bidirectional"))
    )
    (net (code "105") (name "unconnected-(U10-1B3-Pad5)") (class "Default")
      (node (ref "U10") (pin "5") (pinfunction "1B3_5") (pintype "bidirectional"))
    )
    (net (code "106") (name "unconnected-(U10-1B4-Pad6)") (class "Default")
      (node (ref "U10") (pin "6") (pinfunction "1B4_6") (pintype "bidirectional"))
    )
    (net (code "107") (name "unconnected-(U10-1B5-Pad8)") (class "Default")
      (node (ref "U10") (pin "8") (pinfunction "1B5_8") (pintype "bidirectional"))
    )
    (net (code "108") (name "unconnected-(U10-1B6-Pad9)") (class "Default")
      (node (ref "U10") (pin "9") (pinfunction "1B6_9") (pintype "bidirectional"))
    )
    (net (code "109") (name "unconnected-(U10-1B7-Pad11)") (class "Default")
      (node (ref "U10") (pin "11") (pinfunction "1B7_11") (pintype "bidirectional"))
    )
  )
)
